# woda.net
KiCad netlist of a schematic drawn in EAGLE
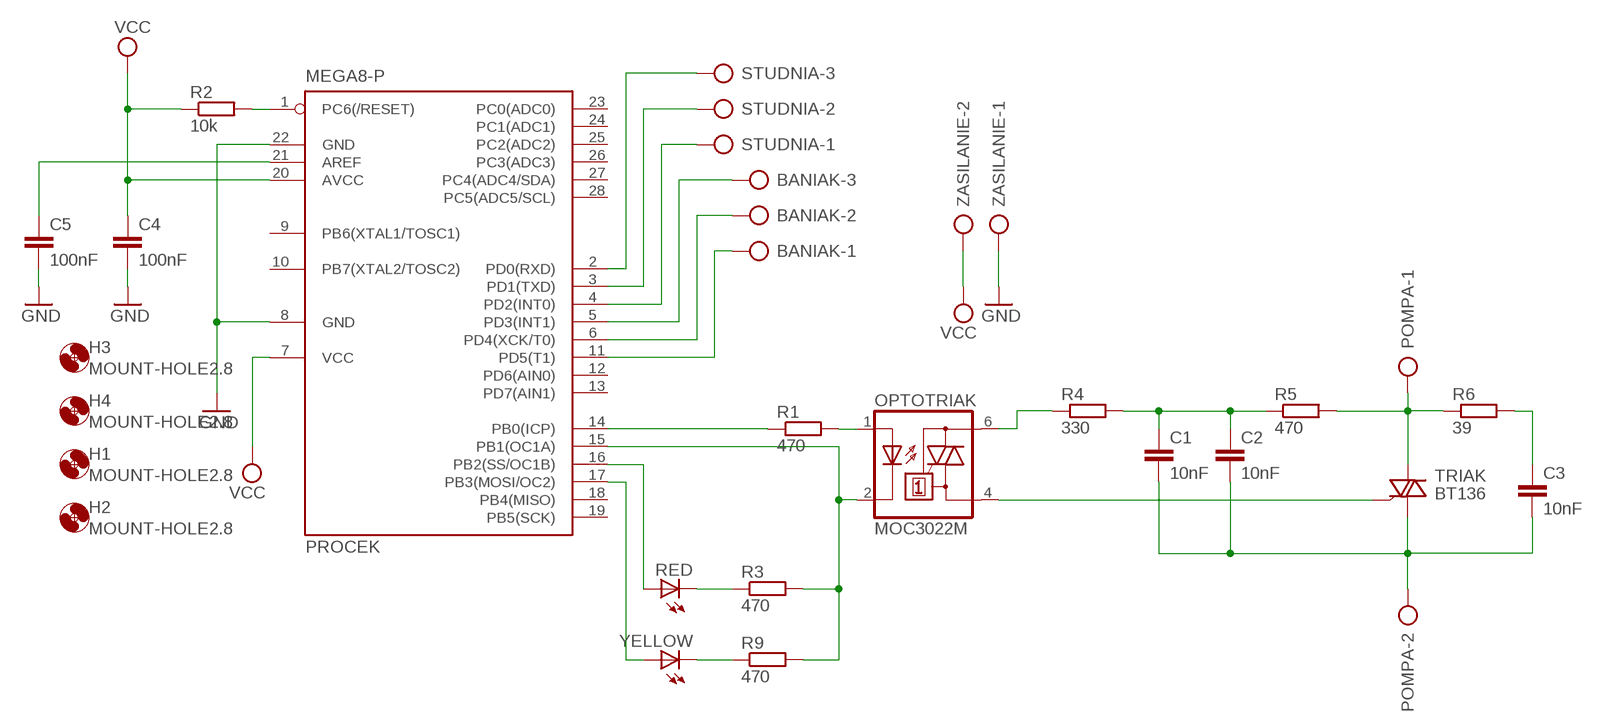
[diagram p0: schematic, sheet 1]

(export (version "E")
  (design (tool "Eeschema 10.0.6"))
  (components
    (comp (ref "BANIAK")
      (value "AK300/3")
      (footprint "eagle-import:AK300_3")
      (libsource (lib "eagle-import") (part "AK300/3"))
    )
    (comp (ref "C1")
      (value "10nF")
      (footprint "eagle-import:C10B4")
      (libsource (lib "eagle-import") (part "C10/4"))
    )
    (comp (ref "C2")
      (value "10nF")
      (footprint "eagle-import:C10B4")
      (libsource (lib "eagle-import") (part "C10/4"))
    )
    (comp (ref "C3")
      (value "10nF")
      (footprint "eagle-import:C10B4")
      (libsource (lib "eagle-import") (part "C10/4"))
    )
    (comp (ref "C4")
      (value "100nF")
      (footprint "eagle-import:C2.5-2")
      (libsource (lib "eagle-import") (part "C2.5/2"))
    )
    (comp (ref "C5")
      (value "100nF")
      (footprint "eagle-import:C2.5-2")
      (libsource (lib "eagle-import") (part "C2.5/2"))
    )
    (comp (ref "H1")
      (value "MOUNT-HOLE2.8")
      (footprint "eagle-import:2,8")
      (libsource (lib "eagle-import") (part "MOUNT-HOLE2.8"))
    )
    (comp (ref "H2")
      (value "MOUNT-HOLE2.8")
      (footprint "eagle-import:2,8")
      (libsource (lib "eagle-import") (part "MOUNT-HOLE2.8"))
    )
    (comp (ref "H3")
      (value "MOUNT-HOLE2.8")
      (footprint "eagle-import:2,8")
      (libsource (lib "eagle-import") (part "MOUNT-HOLE2.8"))
    )
    (comp (ref "H4")
      (value "MOUNT-HOLE2.8")
      (footprint "eagle-import:2,8")
      (libsource (lib "eagle-import") (part "MOUNT-HOLE2.8"))
    )
    (comp (ref "OPTOTRIAK")
      (value "MOC3022M")
      (footprint "eagle-import:DIL06")
      (fields (field (name "MF") "FAIRCHILD SEMICONDUCTOR") (field (name "MPN") "MOC3022-M"))
      (libsource (lib "eagle-import") (part "MOC30M22"))
    )
    (comp (ref "POMPA")
      (value "AK300/2")
      (footprint "eagle-import:AK300_2")
      (libsource (lib "eagle-import") (part "AK300/2"))
    )
    (comp (ref "PROCEK")
      (value "MEGA8-P")
      (footprint "eagle-import:DIL28-3")
      (libsource (lib "eagle-import") (part "MEGA8-P"))
    )
    (comp (ref "R1")
      (value "470")
      (footprint "eagle-import:0207_15")
      (libsource (lib "eagle-import") (part "R-EU_0207/15"))
    )
    (comp (ref "R2")
      (value "10k")
      (footprint "eagle-import:0207_15")
      (libsource (lib "eagle-import") (part "R-EU_0207/15"))
    )
    (comp (ref "R3")
      (value "470")
      (footprint "eagle-import:0207_15")
      (libsource (lib "eagle-import") (part "R-EU_0207/15"))
    )
    (comp (ref "R4")
      (value "330")
      (footprint "eagle-import:0207_7")
      (libsource (lib "eagle-import") (part "R-EU_0207/7"))
    )
    (comp (ref "R5")
      (value "470")
      (footprint "eagle-import:0207_7")
      (libsource (lib "eagle-import") (part "R-EU_0207/7"))
    )
    (comp (ref "R6")
      (value "39")
      (footprint "eagle-import:0207_7")
      (libsource (lib "eagle-import") (part "R-EU_0207/7"))
    )
    (comp (ref "R9")
      (value "470")
      (footprint "eagle-import:0207_15")
      (libsource (lib "eagle-import") (part "R-EU_0207/15"))
    )
    (comp (ref "RED")
      (value "LED3MM")
      (footprint "eagle-import:LED3MM")
      (libsource (lib "eagle-import") (part "LED3MM"))
    )
    (comp (ref "STUDNIA")
      (value "AK300/3")
      (footprint "eagle-import:AK300_3")
      (libsource (lib "eagle-import") (part "AK300/3"))
    )
    (comp (ref "TRIAK")
      (value "BT136")
      (footprint "eagle-import:TO220AB")
      (libsource (lib "eagle-import") (part "BT136"))
    )
    (comp (ref "YELLOW")
      (value "LED3MM")
      (footprint "eagle-import:LED3MM")
      (libsource (lib "eagle-import") (part "LED3MM"))
    )
    (comp (ref "ZASILANIE")
      (value "AK300/2")
      (footprint "eagle-import:AK300_2")
      (libsource (lib "eagle-import") (part "AK300/2"))
    )
  )
  (nets
    (net (code "1") (name "GND") (class "Default")
      (node (ref "C4") (pin "2") (pinfunction "2_2") (pintype "passive"))
      (node (ref "C5") (pin "2") (pinfunction "2_2") (pintype "passive"))
      (node (ref "PROCEK") (pin "22") (pinfunction "GND_22") (pintype "power_in"))
      (node (ref "PROCEK") (pin "8") (pinfunction "GND_8") (pintype "power_in"))
      (node (ref "ZASILANIE") (pin "1") (pinfunction "KL_1") (pintype "passive"))
    )
    (net (code "2") (name "Net-(BANIAKA-KL)") (class "Default")
      (node (ref "BANIAK") (pin "1") (pinfunction "KL_1") (pintype "passive"))
      (node (ref "PROCEK") (pin "11") (pinfunction "PD5(T1)_11") (pintype "bidirectional"))
    )
    (net (code "3") (name "Net-(BANIAKB-KL)") (class "Default")
      (node (ref "BANIAK") (pin "2") (pinfunction "KL_2") (pintype "passive"))
      (node (ref "PROCEK") (pin "6") (pinfunction "PD4(XCK/T0)_6") (pintype "bidirectional"))
    )
    (net (code "4") (name "Net-(BANIAKC-KL)") (class "Default")
      (node (ref "BANIAK") (pin "3") (pinfunction "KL_3") (pintype "passive"))
      (node (ref "PROCEK") (pin "5") (pinfunction "PD3(INT1)_5") (pintype "bidirectional"))
    )
    (net (code "5") (name "Net-(C1-Pad1)") (class "Default")
      (node (ref "C1") (pin "1") (pinfunction "1_1") (pintype "passive"))
      (node (ref "C2") (pin "1") (pinfunction "1_1") (pintype "passive"))
      (node (ref "R4") (pin "2") (pinfunction "2_2") (pintype "passive"))
      (node (ref "R5") (pin "1") (pinfunction "1_1") (pintype "passive"))
    )
    (net (code "6") (name "Net-(C3-Pad1)") (class "Default")
      (node (ref "C3") (pin "1") (pinfunction "1_1") (pintype "passive"))
      (node (ref "R6") (pin "2") (pinfunction "2_2") (pintype "passive"))
    )
    (net (code "7") (name "Net-(OPTOTRIAK-A)") (class "Default")
      (node (ref "OPTOTRIAK") (pin "1") (pinfunction "A_1") (pintype "passive"))
      (node (ref "R1") (pin "2") (pinfunction "2_2") (pintype "passive"))
    )
    (net (code "8") (name "Net-(OPTOTRIAK-A1)") (class "Default")
      (node (ref "OPTOTRIAK") (pin "4") (pinfunction "A1_4") (pintype "passive"))
      (node (ref "TRIAK") (pin "3") (pinfunction "G_3") (pintype "passive"))
    )
    (net (code "9") (name "Net-(OPTOTRIAK-A2)") (class "Default")
      (node (ref "OPTOTRIAK") (pin "6") (pinfunction "A2_6") (pintype "passive"))
      (node (ref "R4") (pin "1") (pinfunction "1_1") (pintype "passive"))
    )
    (net (code "10") (name "Net-(OPTOTRIAK-C)") (class "Default")
      (node (ref "OPTOTRIAK") (pin "2") (pinfunction "C_2") (pintype "passive"))
      (node (ref "PROCEK") (pin "15") (pinfunction "PB1(OC1A)_15") (pintype "bidirectional"))
      (node (ref "R3") (pin "2") (pinfunction "2_2") (pintype "passive"))
      (node (ref "R9") (pin "2") (pinfunction "2_2") (pintype "passive"))
    )
    (net (code "11") (name "Net-(POMPAA-KL)") (class "Default")
      (node (ref "POMPA") (pin "1") (pinfunction "KL_1") (pintype "passive"))
      (node (ref "R5") (pin "2") (pinfunction "2_2") (pintype "passive"))
      (node (ref "R6") (pin "1") (pinfunction "1_1") (pintype "passive"))
      (node (ref "TRIAK") (pin "2") (pinfunction "A2_2") (pintype "passive"))
    )
    (net (code "12") (name "Net-(POMPAB-KL)") (class "Default")
      (node (ref "C1") (pin "2") (pinfunction "2_2") (pintype "passive"))
      (node (ref "C2") (pin "2") (pinfunction "2_2") (pintype "passive"))
      (node (ref "C3") (pin "2") (pinfunction "2_2") (pintype "passive"))
      (node (ref "POMPA") (pin "2") (pinfunction "KL_2") (pintype "passive"))
      (node (ref "TRIAK") (pin "1") (pinfunction "A1_1") (pintype "passive"))
    )
    (net (code "13") (name "Net-(PROCEK-AREF)") (class "Default")
      (node (ref "C5") (pin "1") (pinfunction "1_1") (pintype "passive"))
      (node (ref "PROCEK") (pin "21") (pinfunction "AREF_21") (pintype "passive"))
    )
    (net (code "14") (name "Net-(PROCEK-PB0(ICP))") (class "Default")
      (node (ref "PROCEK") (pin "14") (pinfunction "PB0(ICP)_14") (pintype "bidirectional"))
      (node (ref "R1") (pin "1") (pinfunction "1_1") (pintype "passive"))
    )
    (net (code "15") (name "Net-(PROCEK-PB2(SS{slash}OC1B))") (class "Default")
      (node (ref "PROCEK") (pin "16") (pinfunction "PB2(SS/OC1B)_16") (pintype "bidirectional"))
      (node (ref "RED") (pin "A") (pinfunction "A_A") (pintype "passive"))
    )
    (net (code "16") (name "Net-(PROCEK-PB3(MOSI{slash}OC2))") (class "Default")
      (node (ref "PROCEK") (pin "17") (pinfunction "PB3(MOSI/OC2)_17") (pintype "bidirectional"))
      (node (ref "YELLOW") (pin "A") (pinfunction "A_A") (pintype "passive"))
    )
    (net (code "17") (name "Net-(PROCEK-PC6({slash}RESET))") (class "Default")
      (node (ref "PROCEK") (pin "1") (pinfunction "PC6(/RESET)_1") (pintype "bidirectional"))
      (node (ref "R2") (pin "2") (pinfunction "2_2") (pintype "passive"))
    )
    (net (code "18") (name "Net-(PROCEK-PD0(RXD))") (class "Default")
      (node (ref "PROCEK") (pin "2") (pinfunction "PD0(RXD)_2") (pintype "bidirectional"))
      (node (ref "STUDNIA") (pin "3") (pinfunction "KL_3") (pintype "passive"))
    )
    (net (code "19") (name "Net-(PROCEK-PD1(TXD))") (class "Default")
      (node (ref "PROCEK") (pin "3") (pinfunction "PD1(TXD)_3") (pintype "bidirectional"))
      (node (ref "STUDNIA") (pin "2") (pinfunction "KL_2") (pintype "passive"))
    )
    (net (code "20") (name "Net-(PROCEK-PD2(INT0))") (class "Default")
      (node (ref "PROCEK") (pin "4") (pinfunction "PD2(INT0)_4") (pintype "bidirectional"))
      (node (ref "STUDNIA") (pin "1") (pinfunction "KL_1") (pintype "passive"))
    )
    (net (code "21") (name "Net-(RED-C)") (class "Default")
      (node (ref "R3") (pin "1") (pinfunction "1_1") (pintype "passive"))
      (node (ref "RED") (pin "K") (pinfunction "C_K") (pintype "passive"))
    )
    (net (code "22") (name "Net-(YELLOW-C)") (class "Default")
      (node (ref "R9") (pin "1") (pinfunction "1_1") (pintype "passive"))
      (node (ref "YELLOW") (pin "K") (pinfunction "C_K") (pintype "passive"))
    )
    (net (code "23") (name "VCC") (class "Default")
      (node (ref "C4") (pin "1") (pinfunction "1_1") (pintype "passive"))
      (node (ref "PROCEK") (pin "20") (pinfunction "AVCC_20") (pintype "power_in"))
      (node (ref "PROCEK") (pin "7") (pinfunction "VCC_7") (pintype "power_in"))
      (node (ref "R2") (pin "1") (pinfunction "1_1") (pintype "passive"))
      (node (ref "ZASILANIE") (pin "2") (pinfunction "KL_2") (pintype "passive"))
    )
    (net (code "24") (name "unconnected-(PROCEK-PB4(MISO)-Pad18)") (class "Default")
      (node (ref "PROCEK") (pin "18") (pinfunction "PB4(MISO)_18") (pintype "bidirectional"))
    )
    (net (code "25") (name "unconnected-(PROCEK-PB5(SCK)-Pad19)") (class "Default")
      (node (ref "PROCEK") (pin "19") (pinfunction "PB5(SCK)_19") (pintype "bidirectional"))
    )
    (net (code "26") (name "unconnected-(PROCEK-PB6(XTAL1{slash}TOSC1)-Pad9)") (class "Default")
      (node (ref "PROCEK") (pin "9") (pinfunction "PB6(XTAL1/TOSC1)_9") (pintype "bidirectional"))
    )
    (net (code "27") (name "unconnected-(PROCEK-PB7(XTAL2{slash}TOSC2)-Pad10)") (class "Default")
      (node (ref "PROCEK") (pin "10") (pinfunction "PB7(XTAL2/TOSC2)_10") (pintype "bidirectional"))
    )
    (net (code "28") (name "unconnected-(PROCEK-PC0(ADC0)-Pad23)") (class "Default")
      (node (ref "PROCEK") (pin "23") (pinfunction "PC0(ADC0)_23") (pintype "bidirectional"))
    )
    (net (code "29") (name "unconnected-(PROCEK-PC1(ADC1)-Pad24)") (class "Default")
      (node (ref "PROCEK") (pin "24") (pinfunction "PC1(ADC1)_24") (pintype "bidirectional"))
    )
    (net (code "30") (name "unconnected-(PROCEK-PC2(ADC2)-Pad25)") (class "Default")
      (node (ref "PROCEK") (pin "25") (pinfunction "PC2(ADC2)_25") (pintype "bidirectional"))
    )
    (net (code "31") (name "unconnected-(PROCEK-PC3(ADC3)-Pad26)") (class "Default")
      (node (ref "PROCEK") (pin "26") (pinfunction "PC3(ADC3)_26") (pintype "bidirectional"))
    )
    (net (code "32") (name "unconnected-(PROCEK-PC4(ADC4{slash}SDA)-Pad27)") (class "Default")
      (node (ref "PROCEK") (pin "27") (pinfunction "PC4(ADC4/SDA)_27") (pintype "bidirectional"))
    )
    (net (code "33") (name "unconnected-(PROCEK-PC5(ADC5{slash}SCL)-Pad28)") (class "Default")
      (node (ref "PROCEK") (pin "28") (pinfunction "PC5(ADC5/SCL)_28") (pintype "bidirectional"))
    )
    (net (code "34") (name "unconnected-(PROCEK-PD6(AIN0)-Pad12)") (class "Default")
      (node (ref "PROCEK") (pin "12") (pinfunction "PD6(AIN0)_12") (pintype "bidirectional"))
    )
    (net (code "35") (name "unconnected-(PROCEK-PD7(AIN1)-Pad13)") (class "Default")
      (node (ref "PROCEK") (pin "13") (pinfunction "PD7(AIN1)_13") (pintype "bidirectional"))
    )
  )
)
